# LOGIC_LEVEL_SHIFTER.net
KiCad netlist of a schematic drawn in Altium Designer
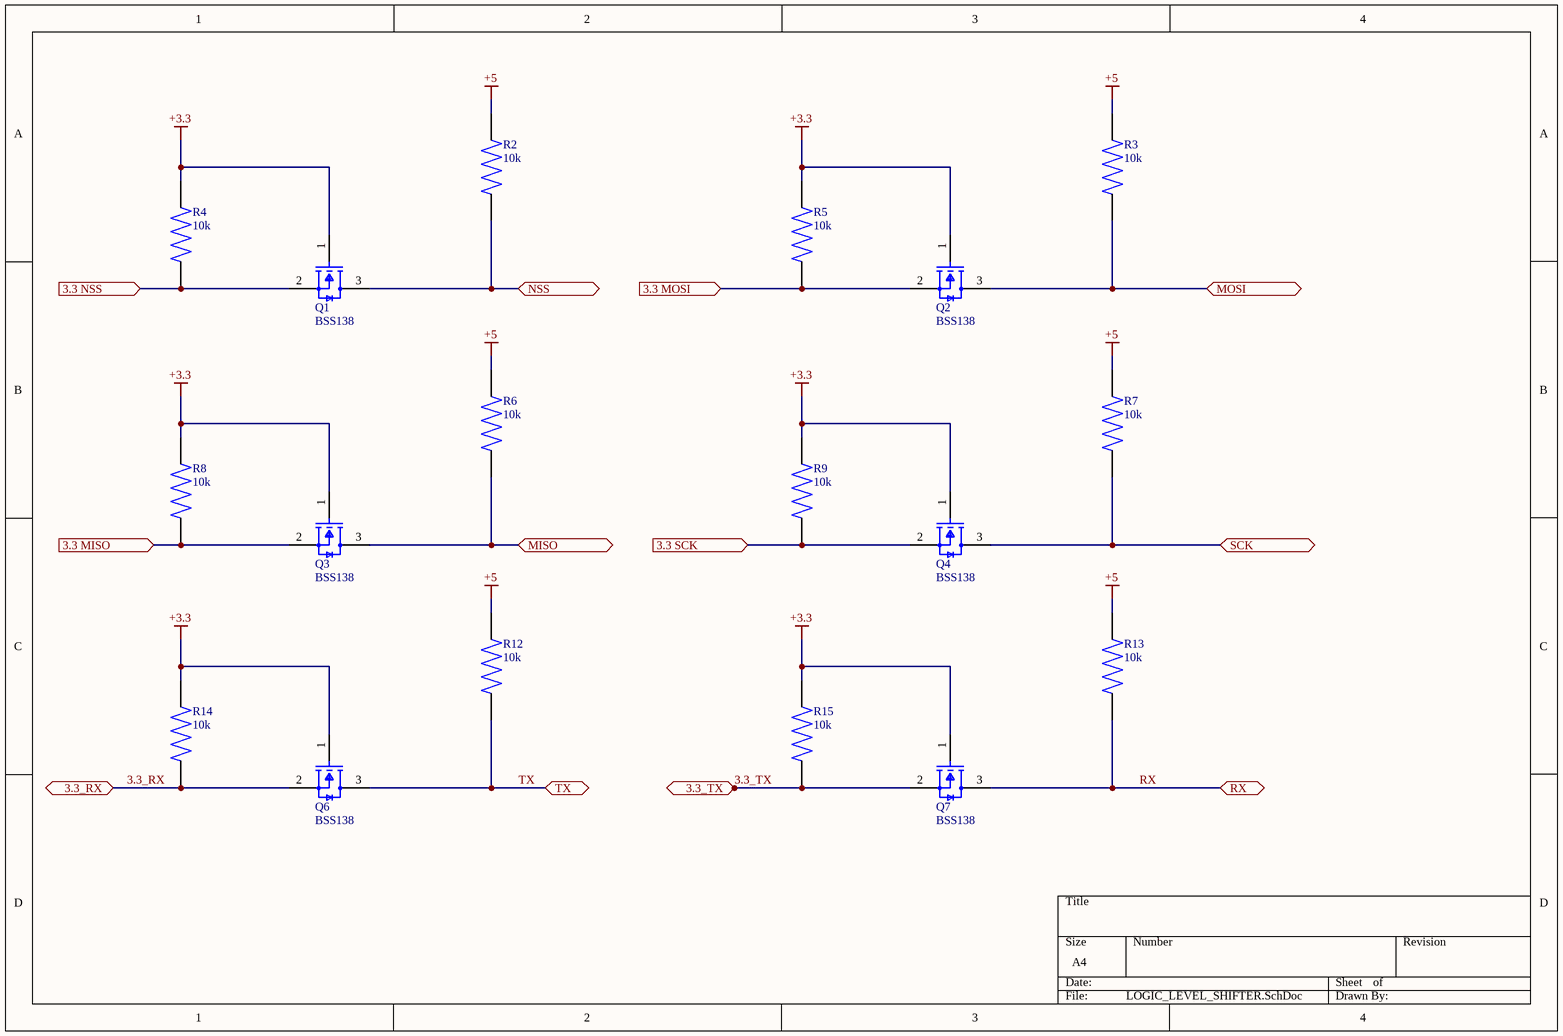
[diagram p0: LOGIC_LEVEL_SHIFTER.SchDoc]

(export (version "E")
  (design (tool "Eeschema 10.0.6"))
  (components
    (comp (ref "Q1")
      (value "BSS138")
      (footprint "FP-318-08-IPC_B")
      (description "MOSFET N-CH 50V 220MA SOT-23")
      (libsource (lib "Altium Content Vault") (part "3b9c635fedb024a5347a57b145af9cc"))
    )
    (comp (ref "Q2")
      (value "BSS138")
      (footprint "FP-318-08-IPC_B")
      (description "MOSFET N-CH 50V 220MA SOT-23")
      (libsource (lib "Altium Content Vault") (part "3b9c635fedb024a5347a57b145af9cc"))
    )
    (comp (ref "Q3")
      (value "BSS138")
      (footprint "FP-318-08-IPC_B")
      (description "MOSFET N-CH 50V 220MA SOT-23")
      (libsource (lib "Altium Content Vault") (part "3b9c635fedb024a5347a57b145af9cc"))
    )
    (comp (ref "Q4")
      (value "BSS138")
      (footprint "FP-318-08-IPC_B")
      (description "MOSFET N-CH 50V 220MA SOT-23")
      (libsource (lib "Altium Content Vault") (part "3b9c635fedb024a5347a57b145af9cc"))
    )
    (comp (ref "Q6")
      (value "BSS138")
      (footprint "FP-318-08-IPC_B")
      (description "MOSFET N-CH 50V 220MA SOT-23")
      (libsource (lib "Altium Content Vault") (part "3b9c635fedb024a5347a57b145af9cc"))
    )
    (comp (ref "Q7")
      (value "BSS138")
      (footprint "FP-318-08-IPC_B")
      (description "MOSFET N-CH 50V 220MA SOT-23")
      (libsource (lib "Altium Content Vault") (part "3b9c635fedb024a5347a57b145af9cc"))
    )
    (comp (ref "R2")
      (value "10k")
      (footprint "RESC3115X65N")
      (description "Res Thick Film 1206 4.7K Ohm 1% 0.25W(1/4W) Â±100ppm/C Pad SMD T/R")
      (fields (field (name "MF") "TE Connectivity") (field (name "MP") "CRG1206F4K7/10"))
      (libsource (lib "RFID") (part "CRG1206F4K7/10"))
    )
    (comp (ref "R3")
      (value "10k")
      (footprint "RESC3115X65N")
      (description "Res Thick Film 1206 4.7K Ohm 1% 0.25W(1/4W) Â±100ppm/C Pad SMD T/R")
      (fields (field (name "MF") "TE Connectivity") (field (name "MP") "CRG1206F4K7/10"))
      (libsource (lib "RFID") (part "CRG1206F4K7/10"))
    )
    (comp (ref "R4")
      (value "10k")
      (footprint "RESC3115X65N")
      (description "Res Thick Film 1206 4.7K Ohm 1% 0.25W(1/4W) Â±100ppm/C Pad SMD T/R")
      (fields (field (name "MF") "TE Connectivity") (field (name "MP") "CRG1206F4K7/10"))
      (libsource (lib "RFID") (part "CRG1206F4K7/10"))
    )
    (comp (ref "R5")
      (value "10k")
      (footprint "RESC3115X65N")
      (description "Res Thick Film 1206 4.7K Ohm 1% 0.25W(1/4W) Â±100ppm/C Pad SMD T/R")
      (fields (field (name "MF") "TE Connectivity") (field (name "MP") "CRG1206F4K7/10"))
      (libsource (lib "RFID") (part "CRG1206F4K7/10"))
    )
    (comp (ref "R6")
      (value "10k")
      (footprint "RESC3115X65N")
      (description "Res Thick Film 1206 4.7K Ohm 1% 0.25W(1/4W) Â±100ppm/C Pad SMD T/R")
      (fields (field (name "MF") "TE Connectivity") (field (name "MP") "CRG1206F4K7/10"))
      (libsource (lib "RFID") (part "CRG1206F4K7/10"))
    )
    (comp (ref "R7")
      (value "10k")
      (footprint "RESC3115X65N")
      (description "Res Thick Film 1206 4.7K Ohm 1% 0.25W(1/4W) Â±100ppm/C Pad SMD T/R")
      (fields (field (name "MF") "TE Connectivity") (field (name "MP") "CRG1206F4K7/10"))
      (libsource (lib "RFID") (part "CRG1206F4K7/10"))
    )
    (comp (ref "R8")
      (value "10k")
      (footprint "RESC3115X65N")
      (description "Res Thick Film 1206 4.7K Ohm 1% 0.25W(1/4W) Â±100ppm/C Pad SMD T/R")
      (fields (field (name "MF") "TE Connectivity") (field (name "MP") "CRG1206F4K7/10"))
      (libsource (lib "RFID") (part "CRG1206F4K7/10"))
    )
    (comp (ref "R9")
      (value "10k")
      (footprint "RESC3115X65N")
      (description "Res Thick Film 1206 4.7K Ohm 1% 0.25W(1/4W) Â±100ppm/C Pad SMD T/R")
      (fields (field (name "MF") "TE Connectivity") (field (name "MP") "CRG1206F4K7/10"))
      (libsource (lib "RFID") (part "CRG1206F4K7/10"))
    )
    (comp (ref "R12")
      (value "10k")
      (footprint "RESC3115X65N")
      (description "Res Thick Film 1206 4.7K Ohm 1% 0.25W(1/4W) Â±100ppm/C Pad SMD T/R")
      (fields (field (name "MF") "TE Connectivity") (field (name "MP") "CRG1206F4K7/10"))
      (libsource (lib "RFID") (part "CRG1206F4K7/10"))
    )
    (comp (ref "R13")
      (value "10k")
      (footprint "RESC3115X65N")
      (description "Res Thick Film 1206 4.7K Ohm 1% 0.25W(1/4W) Â±100ppm/C Pad SMD T/R")
      (fields (field (name "MF") "TE Connectivity") (field (name "MP") "CRG1206F4K7/10"))
      (libsource (lib "RFID") (part "CRG1206F4K7/10"))
    )
    (comp (ref "R14")
      (value "10k")
      (footprint "RESC3115X65N")
      (description "Res Thick Film 1206 4.7K Ohm 1% 0.25W(1/4W) Â±100ppm/C Pad SMD T/R")
      (fields (field (name "MF") "TE Connectivity") (field (name "MP") "CRG1206F4K7/10"))
      (libsource (lib "RFID") (part "CRG1206F4K7/10"))
    )
    (comp (ref "R15")
      (value "10k")
      (footprint "RESC3115X65N")
      (description "Res Thick Film 1206 4.7K Ohm 1% 0.25W(1/4W) Â±100ppm/C Pad SMD T/R")
      (fields (field (name "MF") "TE Connectivity") (field (name "MP") "CRG1206F4K7/10"))
      (libsource (lib "RFID") (part "CRG1206F4K7/10"))
    )
  )
  (nets
    (net (code "1") (name "+3.3") (class "Default")
      (node (ref "Q1") (pin "1") (pinfunction "G_1") (pintype "passive"))
      (node (ref "Q2") (pin "1") (pinfunction "G_1") (pintype "passive"))
      (node (ref "Q3") (pin "1") (pinfunction "G_1") (pintype "passive"))
      (node (ref "Q4") (pin "1") (pinfunction "G_1") (pintype "passive"))
      (node (ref "Q6") (pin "1") (pinfunction "G_1") (pintype "passive"))
      (node (ref "Q7") (pin "1") (pinfunction "G_1") (pintype "passive"))
      (node (ref "R14") (pin "2") (pinfunction "2_2") (pintype "passive"))
      (node (ref "R15") (pin "2") (pinfunction "2_2") (pintype "passive"))
      (node (ref "R4") (pin "2") (pinfunction "2_2") (pintype "passive"))
      (node (ref "R5") (pin "2") (pinfunction "2_2") (pintype "passive"))
      (node (ref "R8") (pin "2") (pinfunction "2_2") (pintype "passive"))
      (node (ref "R9") (pin "2") (pinfunction "2_2") (pintype "passive"))
    )
    (net (code "2") (name "+5") (class "Default")
      (node (ref "R12") (pin "2") (pinfunction "2_2") (pintype "passive"))
      (node (ref "R13") (pin "2") (pinfunction "2_2") (pintype "passive"))
      (node (ref "R2") (pin "2") (pinfunction "2_2") (pintype "passive"))
      (node (ref "R3") (pin "2") (pinfunction "2_2") (pintype "passive"))
      (node (ref "R6") (pin "2") (pinfunction "2_2") (pintype "passive"))
      (node (ref "R7") (pin "2") (pinfunction "2_2") (pintype "passive"))
    )
    (net (code "3") (name "/3.3 MISO") (class "Default")
      (node (ref "Q3") (pin "2") (pinfunction "S_2") (pintype "passive"))
      (node (ref "R8") (pin "1") (pinfunction "1_1") (pintype "passive"))
    )
    (net (code "4") (name "/3.3 MOSI") (class "Default")
      (node (ref "Q2") (pin "2") (pinfunction "S_2") (pintype "passive"))
      (node (ref "R5") (pin "1") (pinfunction "1_1") (pintype "passive"))
    )
    (net (code "5") (name "/3.3 NSS") (class "Default")
      (node (ref "Q1") (pin "2") (pinfunction "S_2") (pintype "passive"))
      (node (ref "R4") (pin "1") (pinfunction "1_1") (pintype "passive"))
    )
    (net (code "6") (name "/3.3 SCK") (class "Default")
      (node (ref "Q4") (pin "2") (pinfunction "S_2") (pintype "passive"))
      (node (ref "R9") (pin "1") (pinfunction "1_1") (pintype "passive"))
    )
    (net (code "7") (name "/3.3_RX") (class "Default")
      (node (ref "Q6") (pin "2") (pinfunction "S_2") (pintype "passive"))
      (node (ref "R14") (pin "1") (pinfunction "1_1") (pintype "passive"))
    )
    (net (code "8") (name "/3.3_TX") (class "Default")
      (node (ref "Q7") (pin "2") (pinfunction "S_2") (pintype "passive"))
      (node (ref "R15") (pin "1") (pinfunction "1_1") (pintype "passive"))
    )
    (net (code "9") (name "/MISO") (class "Default")
      (node (ref "Q3") (pin "3") (pinfunction "D_3") (pintype "passive"))
      (node (ref "R6") (pin "1") (pinfunction "1_1") (pintype "passive"))
    )
    (net (code "10") (name "/MOSI") (class "Default")
      (node (ref "Q2") (pin "3") (pinfunction "D_3") (pintype "passive"))
      (node (ref "R3") (pin "1") (pinfunction "1_1") (pintype "passive"))
    )
    (net (code "11") (name "/NSS") (class "Default")
      (node (ref "Q1") (pin "3") (pinfunction "D_3") (pintype "passive"))
      (node (ref "R2") (pin "1") (pinfunction "1_1") (pintype "passive"))
    )
    (net (code "12") (name "/RX") (class "Default")
      (node (ref "Q7") (pin "3") (pinfunction "D_3") (pintype "passive"))
      (node (ref "R13") (pin "1") (pinfunction "1_1") (pintype "passive"))
    )
    (net (code "13") (name "/SCK") (class "Default")
      (node (ref "Q4") (pin "3") (pinfunction "D_3") (pintype "passive"))
      (node (ref "R7") (pin "1") (pinfunction "1_1") (pintype "passive"))
    )
    (net (code "14") (name "/TX") (class "Default")
      (node (ref "Q6") (pin "3") (pinfunction "D_3") (pintype "passive"))
      (node (ref "R12") (pin "1") (pinfunction "1_1") (pintype "passive"))
    )
  )
)
